# SCH_555-circuit_2025-11-09.net
KiCad netlist of a schematic drawn in EasyEDA
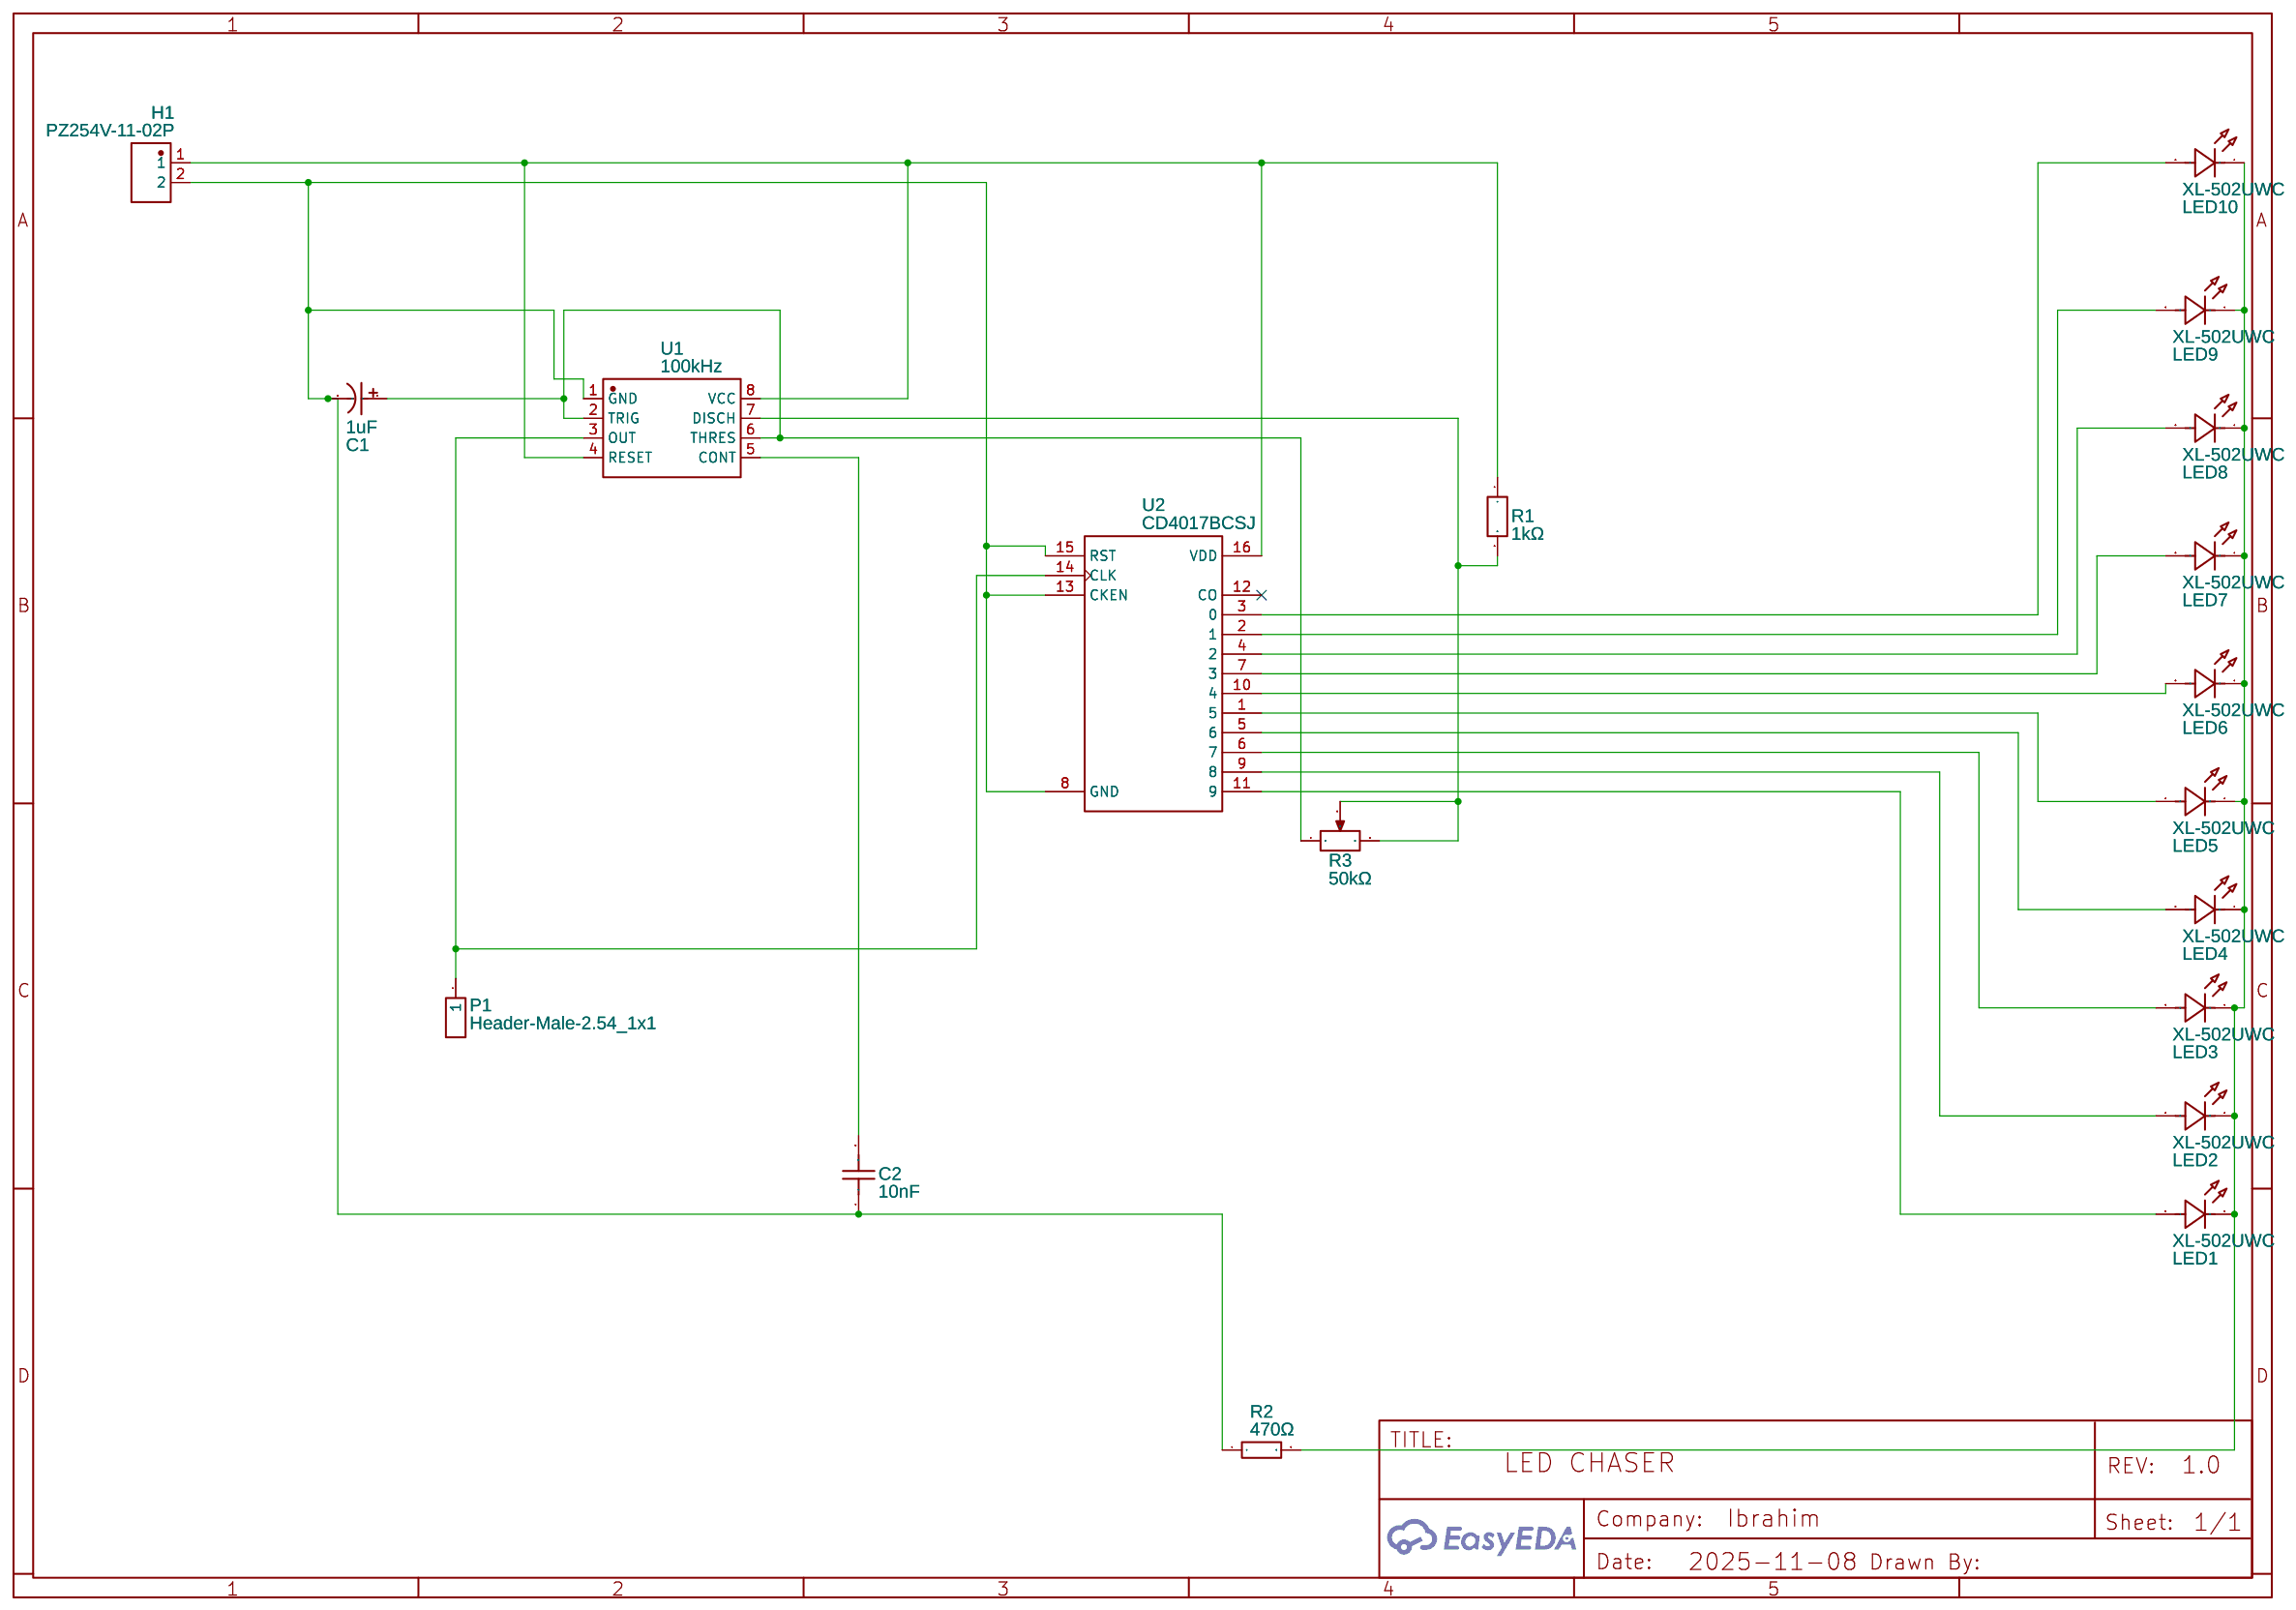
[diagram p0: schematic sheet]

(export (version "E")
  (design (tool "Eeschema 10.0.6"))
  (components
    (comp (ref "C1")
      (value "1uF")
      (fields (field (name "Manufacturer Part") "KF010M050C110A") (field (name "Manufacturer") "CapXon(丰宾)"))
      (libsource (lib "") (part "KF010M050C110A"))
    )
    (comp (ref "C2")
      (value "10nF")
      (fields (field (name "Manufacturer Part") "N09F1B103MN0B0S0N0") (field (name "Manufacturer") "STE(松田)"))
      (libsource (lib "") (part "N09F1B103MN0B0S0N0"))
    )
    (comp (ref "H1")
      (value "PZ254V-11-02P")
      (fields (field (name "Manufacturer") "XFCN(兴飞)"))
      (libsource (lib "") (part "PZ254V-11-02P"))
    )
    (comp (ref "LED1")
      (value "XL-502UWC")
      (fields (field (name "Manufacturer") "XINGLIGHT(成兴光)"))
      (libsource (lib "") (part "XL-502UWC"))
    )
    (comp (ref "LED2")
      (value "XL-502UWC")
      (fields (field (name "Manufacturer") "XINGLIGHT(成兴光)"))
      (libsource (lib "") (part "XL-502UWC"))
    )
    (comp (ref "LED3")
      (value "XL-502UWC")
      (fields (field (name "Manufacturer") "XINGLIGHT(成兴光)"))
      (libsource (lib "") (part "XL-502UWC"))
    )
    (comp (ref "LED4")
      (value "XL-502UWC")
      (fields (field (name "Manufacturer") "XINGLIGHT(成兴光)"))
      (libsource (lib "") (part "XL-502UWC"))
    )
    (comp (ref "LED5")
      (value "XL-502UWC")
      (fields (field (name "Manufacturer") "XINGLIGHT(成兴光)"))
      (libsource (lib "") (part "XL-502UWC"))
    )
    (comp (ref "LED6")
      (value "XL-502UWC")
      (fields (field (name "Manufacturer") "XINGLIGHT(成兴光)"))
      (libsource (lib "") (part "XL-502UWC"))
    )
    (comp (ref "LED7")
      (value "XL-502UWC")
      (fields (field (name "Manufacturer") "XINGLIGHT(成兴光)"))
      (libsource (lib "") (part "XL-502UWC"))
    )
    (comp (ref "LED8")
      (value "XL-502UWC")
      (fields (field (name "Manufacturer") "XINGLIGHT(成兴光)"))
      (libsource (lib "") (part "XL-502UWC"))
    )
    (comp (ref "LED9")
      (value "XL-502UWC")
      (fields (field (name "Manufacturer") "XINGLIGHT(成兴光)"))
      (libsource (lib "") (part "XL-502UWC"))
    )
    (comp (ref "LED10")
      (value "XL-502UWC")
      (fields (field (name "Manufacturer") "XINGLIGHT(成兴光)"))
      (libsource (lib "") (part "XL-502UWC"))
    )
    (comp (ref "P1")
      (value "Header-Male-2.54_1x1")
      (fields (field (name "Manufacturer Part") "2.54-1*1P针") (field (name "Manufacturer") "BOOMELE(博穆精密)"))
      (libsource (lib "") (part "Header-Male-2.54_1x1"))
    )
    (comp (ref "R1")
      (value "1kΩ")
      (fields (field (name "Manufacturer Part") "MF1/4W-1KΩ±1%T52") (field (name "Manufacturer") "华星机电"))
      (libsource (lib "") (part "MF1/4W-1KΩ±1%T52"))
    )
    (comp (ref "R2")
      (value "470Ω")
      (fields
        (field (name "Manufacturer Part") "MFR0W4F4700A50")
        (field (name "Manufacturer") "UNI-ROYAL(厚声)")
      )
      (libsource (lib "") (part "MFR0W4F4700A50"))
    )
    (comp (ref "R3")
      (value "50kΩ")
      (fields (field (name "Manufacturer Part") "3296X-1-503") (field (name "Manufacturer") "BOCHEN(博晨)"))
      (libsource (lib "") (part "3296X-1-503_C118912"))
    )
    (comp (ref "U1")
      (value "100kHz")
      (fields (field (name "Manufacturer Part") "NE555P") (field (name "Manufacturer") "TI(德州仪器)"))
      (libsource (lib "") (part "NE555P"))
    )
    (comp (ref "U2") (value "CD4017BCSJ") (libsource (lib "") (part "CD4017BCSJ")))
  )
  (nets
    (net (code "1") (name "Net-(LED1-A)") (class "Default")
      (node (ref "LED1") (pin "2") (pinfunction "A_2") (pintype "unspecified"))
      (node (ref "U2") (pin "11") (pinfunction "9_11") (pintype "output"))
    )
    (net (code "2") (name "Net-(LED1-K)") (class "Default")
      (node (ref "LED1") (pin "1") (pinfunction "K_1") (pintype "unspecified"))
      (node (ref "LED10") (pin "1") (pinfunction "K_1") (pintype "unspecified"))
      (node (ref "LED2") (pin "1") (pinfunction "K_1") (pintype "unspecified"))
      (node (ref "LED3") (pin "1") (pinfunction "K_1") (pintype "unspecified"))
      (node (ref "LED4") (pin "1") (pinfunction "K_1") (pintype "unspecified"))
      (node (ref "LED5") (pin "1") (pinfunction "K_1") (pintype "unspecified"))
      (node (ref "LED6") (pin "1") (pinfunction "K_1") (pintype "unspecified"))
      (node (ref "LED7") (pin "1") (pinfunction "K_1") (pintype "unspecified"))
      (node (ref "LED8") (pin "1") (pinfunction "K_1") (pintype "unspecified"))
      (node (ref "LED9") (pin "1") (pinfunction "K_1") (pintype "unspecified"))
      (node (ref "R2") (pin "2") (pinfunction "2_2") (pintype "input"))
    )
    (net (code "3") (name "Net-(LED2-A)") (class "Default")
      (node (ref "LED2") (pin "2") (pinfunction "A_2") (pintype "unspecified"))
      (node (ref "U2") (pin "9") (pinfunction "8_9") (pintype "output"))
    )
    (net (code "4") (name "Net-(LED3-A)") (class "Default")
      (node (ref "LED3") (pin "2") (pinfunction "A_2") (pintype "unspecified"))
      (node (ref "U2") (pin "6") (pinfunction "7_6") (pintype "output"))
    )
    (net (code "5") (name "Net-(LED4-A)") (class "Default")
      (node (ref "LED4") (pin "2") (pinfunction "A_2") (pintype "unspecified"))
      (node (ref "U2") (pin "5") (pinfunction "6_5") (pintype "output"))
    )
    (net (code "6") (name "Net-(LED5-A)") (class "Default")
      (node (ref "LED5") (pin "2") (pinfunction "A_2") (pintype "unspecified"))
      (node (ref "U2") (pin "1") (pinfunction "5_1") (pintype "output"))
    )
    (net (code "7") (name "Net-(LED6-A)") (class "Default")
      (node (ref "LED6") (pin "2") (pinfunction "A_2") (pintype "unspecified"))
      (node (ref "U2") (pin "10") (pinfunction "4_10") (pintype "output"))
    )
    (net (code "8") (name "Net-(LED7-A)") (class "Default")
      (node (ref "LED7") (pin "2") (pinfunction "A_2") (pintype "unspecified"))
      (node (ref "U2") (pin "7") (pinfunction "3_7") (pintype "output"))
    )
    (net (code "9") (name "Net-(LED8-A)") (class "Default")
      (node (ref "LED8") (pin "2") (pinfunction "A_2") (pintype "unspecified"))
      (node (ref "U2") (pin "4") (pinfunction "2_4") (pintype "output"))
    )
    (net (code "10") (name "Net-(LED9-A)") (class "Default")
      (node (ref "LED9") (pin "2") (pinfunction "A_2") (pintype "unspecified"))
      (node (ref "U2") (pin "2") (pinfunction "1_2") (pintype "output"))
    )
    (net (code "11") (name "Net-(LED10-A)") (class "Default")
      (node (ref "LED10") (pin "2") (pinfunction "A_2") (pintype "unspecified"))
      (node (ref "U2") (pin "3") (pinfunction "0_3") (pintype "output"))
    )
    (net (code "12") (name "Net-(U1-CONT)") (class "Default")
      (node (ref "C2") (pin "2") (pinfunction "2_2") (pintype "unspecified"))
      (node (ref "U1") (pin "5") (pinfunction "CONT_5") (pintype "unspecified"))
    )
    (net (code "13") (name "Net-(U1-DISCH)") (class "Default")
      (node (ref "R1") (pin "2") (pinfunction "2_2") (pintype "unspecified"))
      (node (ref "R3") (pin "2") (pinfunction "2_2") (pintype "input"))
      (node (ref "R3") (pin "3") (pinfunction "3_3") (pintype "input"))
      (node (ref "U1") (pin "7") (pinfunction "DISCH_7") (pintype "unspecified"))
    )
    (net (code "14") (name "Net-(U1-GND)") (class "Default")
      (node (ref "C1") (pin "2") (pinfunction "2_2") (pintype "input"))
      (node (ref "C2") (pin "1") (pinfunction "1_1") (pintype "unspecified"))
      (node (ref "H1") (pin "2") (pinfunction "2_2") (pintype "unspecified"))
      (node (ref "R2") (pin "1") (pinfunction "1_1") (pintype "input"))
      (node (ref "U1") (pin "1") (pinfunction "GND_1") (pintype "unspecified"))
      (node (ref "U2") (pin "13") (pinfunction "CKEN_13") (pintype "unspecified"))
      (node (ref "U2") (pin "15") (pinfunction "RST_15") (pintype "unspecified"))
      (node (ref "U2") (pin "8") (pinfunction "GND_8") (pintype "passive"))
    )
    (net (code "15") (name "Net-(U1-OUT)") (class "Default")
      (node (ref "P1") (pin "1") (pinfunction "1_1") (pintype "input"))
      (node (ref "U1") (pin "3") (pinfunction "OUT_3") (pintype "unspecified"))
      (node (ref "U2") (pin "14") (pinfunction "CLK_14") (pintype "unspecified"))
    )
    (net (code "16") (name "Net-(U1-RESET)") (class "Default")
      (node (ref "H1") (pin "1") (pinfunction "1_1") (pintype "unspecified"))
      (node (ref "R1") (pin "1") (pinfunction "1_1") (pintype "unspecified"))
      (node (ref "U1") (pin "4") (pinfunction "RESET_4") (pintype "unspecified"))
      (node (ref "U1") (pin "8") (pinfunction "VCC_8") (pintype "unspecified"))
      (node (ref "U2") (pin "16") (pinfunction "VDD_16") (pintype "passive"))
    )
    (net (code "17") (name "Net-(U1-THRES)") (class "Default")
      (node (ref "C1") (pin "1") (pinfunction "1_1") (pintype "input"))
      (node (ref "R3") (pin "1") (pinfunction "1_1") (pintype "input"))
      (node (ref "U1") (pin "2") (pinfunction "TRIG_2") (pintype "unspecified"))
      (node (ref "U1") (pin "6") (pinfunction "THRES_6") (pintype "unspecified"))
    )
    (net (code "18") (name "unconnected-(U2-CO-Pad12)") (class "Default")
      (node (ref "U2") (pin "12") (pinfunction "CO_12") (pintype "output+no_connect"))
    )
  )
)
